# Circuito3Led.net
KiCad netlist of a schematic drawn in EAGLE
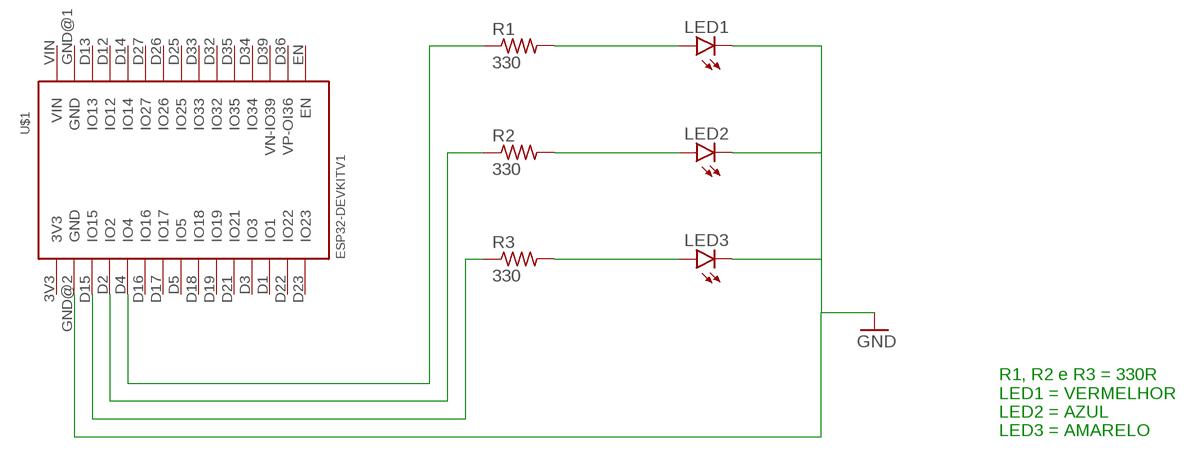
[diagram p0: schematic, sheet 1]

(export (version "E")
  (design (tool "Eeschema 10.0.6"))
  (components
    (comp (ref "LED1")
      (value "LED5MM")
      (footprint "eagle-import:LED5MM")
      (libsource (lib "eagle-import") (part "LED5MM"))
    )
    (comp (ref "LED2")
      (value "LED5MM")
      (footprint "eagle-import:LED5MM")
      (libsource (lib "eagle-import") (part "LED5MM"))
    )
    (comp (ref "LED3")
      (value "LED5MM")
      (footprint "eagle-import:LED5MM")
      (libsource (lib "eagle-import") (part "LED5MM"))
    )
    (comp (ref "R1")
      (value "330")
      (footprint "eagle-import:0204_7")
      (libsource (lib "eagle-import") (part "R-US_0204/7"))
    )
    (comp (ref "R2")
      (value "330")
      (footprint "eagle-import:0204_7")
      (libsource (lib "eagle-import") (part "R-US_0204/7"))
    )
    (comp (ref "R3")
      (value "330")
      (footprint "eagle-import:0204_7")
      (libsource (lib "eagle-import") (part "R-US_0204/7"))
    )
    (comp (ref "U$1")
      (value "ESP32DEVKITV1")
      (footprint "eagle-import:ESP32-DEVKITV1")
      (libsource (lib "eagle-import") (part "ESP32DEVKITV1"))
    )
  )
  (nets
    (net (code "1") (name "GND") (class "Default")
      (node (ref "LED1") (pin "K") (pinfunction "C_K") (pintype "passive"))
      (node (ref "LED2") (pin "K") (pinfunction "C_K") (pintype "passive"))
      (node (ref "LED3") (pin "K") (pinfunction "C_K") (pintype "passive"))
      (node (ref "U$1") (pin "GND@2") (pinfunction "GND_GND@2") (pintype "bidirectional"))
    )
    (net (code "2") (name "Net-(LED1-PadA)") (class "Default")
      (node (ref "LED1") (pin "A") (pinfunction "A_A") (pintype "passive"))
      (node (ref "R1") (pin "2") (pinfunction "2_2") (pintype "passive"))
    )
    (net (code "3") (name "Net-(LED2-PadA)") (class "Default")
      (node (ref "LED2") (pin "A") (pinfunction "A_A") (pintype "passive"))
      (node (ref "R2") (pin "2") (pinfunction "2_2") (pintype "passive"))
    )
    (net (code "4") (name "Net-(LED3-PadA)") (class "Default")
      (node (ref "LED3") (pin "A") (pinfunction "A_A") (pintype "passive"))
      (node (ref "R3") (pin "2") (pinfunction "2_2") (pintype "passive"))
    )
    (net (code "5") (name "Net-(U$1-IO2)") (class "Default")
      (node (ref "R2") (pin "1") (pinfunction "1_1") (pintype "passive"))
      (node (ref "U$1") (pin "D2") (pinfunction "IO2_D2") (pintype "bidirectional"))
    )
    (net (code "6") (name "Net-(U$1-IO4)") (class "Default")
      (node (ref "R1") (pin "1") (pinfunction "1_1") (pintype "passive"))
      (node (ref "U$1") (pin "D4") (pinfunction "IO4_D4") (pintype "bidirectional"))
    )
    (net (code "7") (name "Net-(U$1-IO15)") (class "Default")
      (node (ref "R3") (pin "1") (pinfunction "1_1") (pintype "passive"))
      (node (ref "U$1") (pin "D15") (pinfunction "IO15_D15") (pintype "bidirectional"))
    )
    (net (code "8") (name "unconnected-(U$1-GND-PadGND@1)") (class "Default")
      (node (ref "U$1") (pin "GND@1") (pinfunction "GND_GND@1") (pintype "bidirectional"))
    )
    (net (code "9") (name "unconnected-(U$1-IO1-PadD1)") (class "Default")
      (node (ref "U$1") (pin "D1") (pinfunction "IO1_D1") (pintype "bidirectional"))
    )
    (net (code "10") (name "unconnected-(U$1-IO3-PadD3)") (class "Default")
      (node (ref "U$1") (pin "D3") (pinfunction "IO3_D3") (pintype "bidirectional"))
    )
    (net (code "11") (name "unconnected-(U$1-IO5-PadD5)") (class "Default")
      (node (ref "U$1") (pin "D5") (pinfunction "IO5_D5") (pintype "bidirectional"))
    )
    (net (code "12") (name "unconnected-(U$1-IO12-PadD12)") (class "Default")
      (node (ref "U$1") (pin "D12") (pinfunction "IO12_D12") (pintype "bidirectional"))
    )
    (net (code "13") (name "unconnected-(U$1-IO13-PadD13)") (class "Default")
      (node (ref "U$1") (pin "D13") (pinfunction "IO13_D13") (pintype "bidirectional"))
    )
    (net (code "14") (name "unconnected-(U$1-IO14-PadD14)") (class "Default")
      (node (ref "U$1") (pin "D14") (pinfunction "IO14_D14") (pintype "bidirectional"))
    )
    (net (code "15") (name "unconnected-(U$1-IO16-PadD16)") (class "Default")
      (node (ref "U$1") (pin "D16") (pinfunction "IO16_D16") (pintype "bidirectional"))
    )
    (net (code "16") (name "unconnected-(U$1-IO17-PadD17)") (class "Default")
      (node (ref "U$1") (pin "D17") (pinfunction "IO17_D17") (pintype "bidirectional"))
    )
    (net (code "17") (name "unconnected-(U$1-IO18-PadD18)") (class "Default")
      (node (ref "U$1") (pin "D18") (pinfunction "IO18_D18") (pintype "bidirectional"))
    )
    (net (code "18") (name "unconnected-(U$1-IO19-PadD19)") (class "Default")
      (node (ref "U$1") (pin "D19") (pinfunction "IO19_D19") (pintype "bidirectional"))
    )
    (net (code "19") (name "unconnected-(U$1-IO21-PadD21)") (class "Default")
      (node (ref "U$1") (pin "D21") (pinfunction "IO21_D21") (pintype "bidirectional"))
    )
    (net (code "20") (name "unconnected-(U$1-IO22-PadD22)") (class "Default")
      (node (ref "U$1") (pin "D22") (pinfunction "IO22_D22") (pintype "bidirectional"))
    )
    (net (code "21") (name "unconnected-(U$1-IO23-PadD23)") (class "Default")
      (node (ref "U$1") (pin "D23") (pinfunction "IO23_D23") (pintype "bidirectional"))
    )
    (net (code "22") (name "unconnected-(U$1-IO25-PadD25)") (class "Default")
      (node (ref "U$1") (pin "D25") (pinfunction "IO25_D25") (pintype "bidirectional"))
    )
    (net (code "23") (name "unconnected-(U$1-IO26-PadD26)") (class "Default")
      (node (ref "U$1") (pin "D26") (pinfunction "IO26_D26") (pintype "bidirectional"))
    )
    (net (code "24") (name "unconnected-(U$1-IO27-PadD27)") (class "Default")
      (node (ref "U$1") (pin "D27") (pinfunction "IO27_D27") (pintype "bidirectional"))
    )
    (net (code "25") (name "unconnected-(U$1-IO32-PadD32)") (class "Default")
      (node (ref "U$1") (pin "D32") (pinfunction "IO32_D32") (pintype "bidirectional"))
    )
    (net (code "26") (name "unconnected-(U$1-IO33-PadD33)") (class "Default")
      (node (ref "U$1") (pin "D33") (pinfunction "IO33_D33") (pintype "bidirectional"))
    )
    (net (code "27") (name "unconnected-(U$1-IO34-PadD34)") (class "Default")
      (node (ref "U$1") (pin "D34") (pinfunction "IO34_D34") (pintype "bidirectional"))
    )
    (net (code "28") (name "unconnected-(U$1-IO35-PadD35)") (class "Default")
      (node (ref "U$1") (pin "D35") (pinfunction "IO35_D35") (pintype "bidirectional"))
    )
    (net (code "29") (name "unconnected-(U$1-Pad3V3)") (class "Default")
      (node (ref "U$1") (pin "3V3") (pinfunction "3V3_3V3") (pintype "bidirectional"))
    )
    (net (code "30") (name "unconnected-(U$1-PadEN)") (class "Default")
      (node (ref "U$1") (pin "EN") (pinfunction "EN_EN") (pintype "bidirectional"))
    )
    (net (code "31") (name "unconnected-(U$1-PadVIN)") (class "Default")
      (node (ref "U$1") (pin "VIN") (pinfunction "VIN_VIN") (pintype "bidirectional"))
    )
    (net (code "32") (name "unconnected-(U$1-VN-IO39-PadD39)") (class "Default")
      (node (ref "U$1") (pin "D39") (pinfunction "VN-IO39_D39") (pintype "bidirectional"))
    )
    (net (code "33") (name "unconnected-(U$1-VP-OI36-PadD36)") (class "Default")
      (node (ref "U$1") (pin "D36") (pinfunction "VP-OI36_D36") (pintype "bidirectional"))
    )
  )
)
